# interfacez_vgaaudio_r2_0.net
KiCad netlist of a schematic drawn in EAGLE
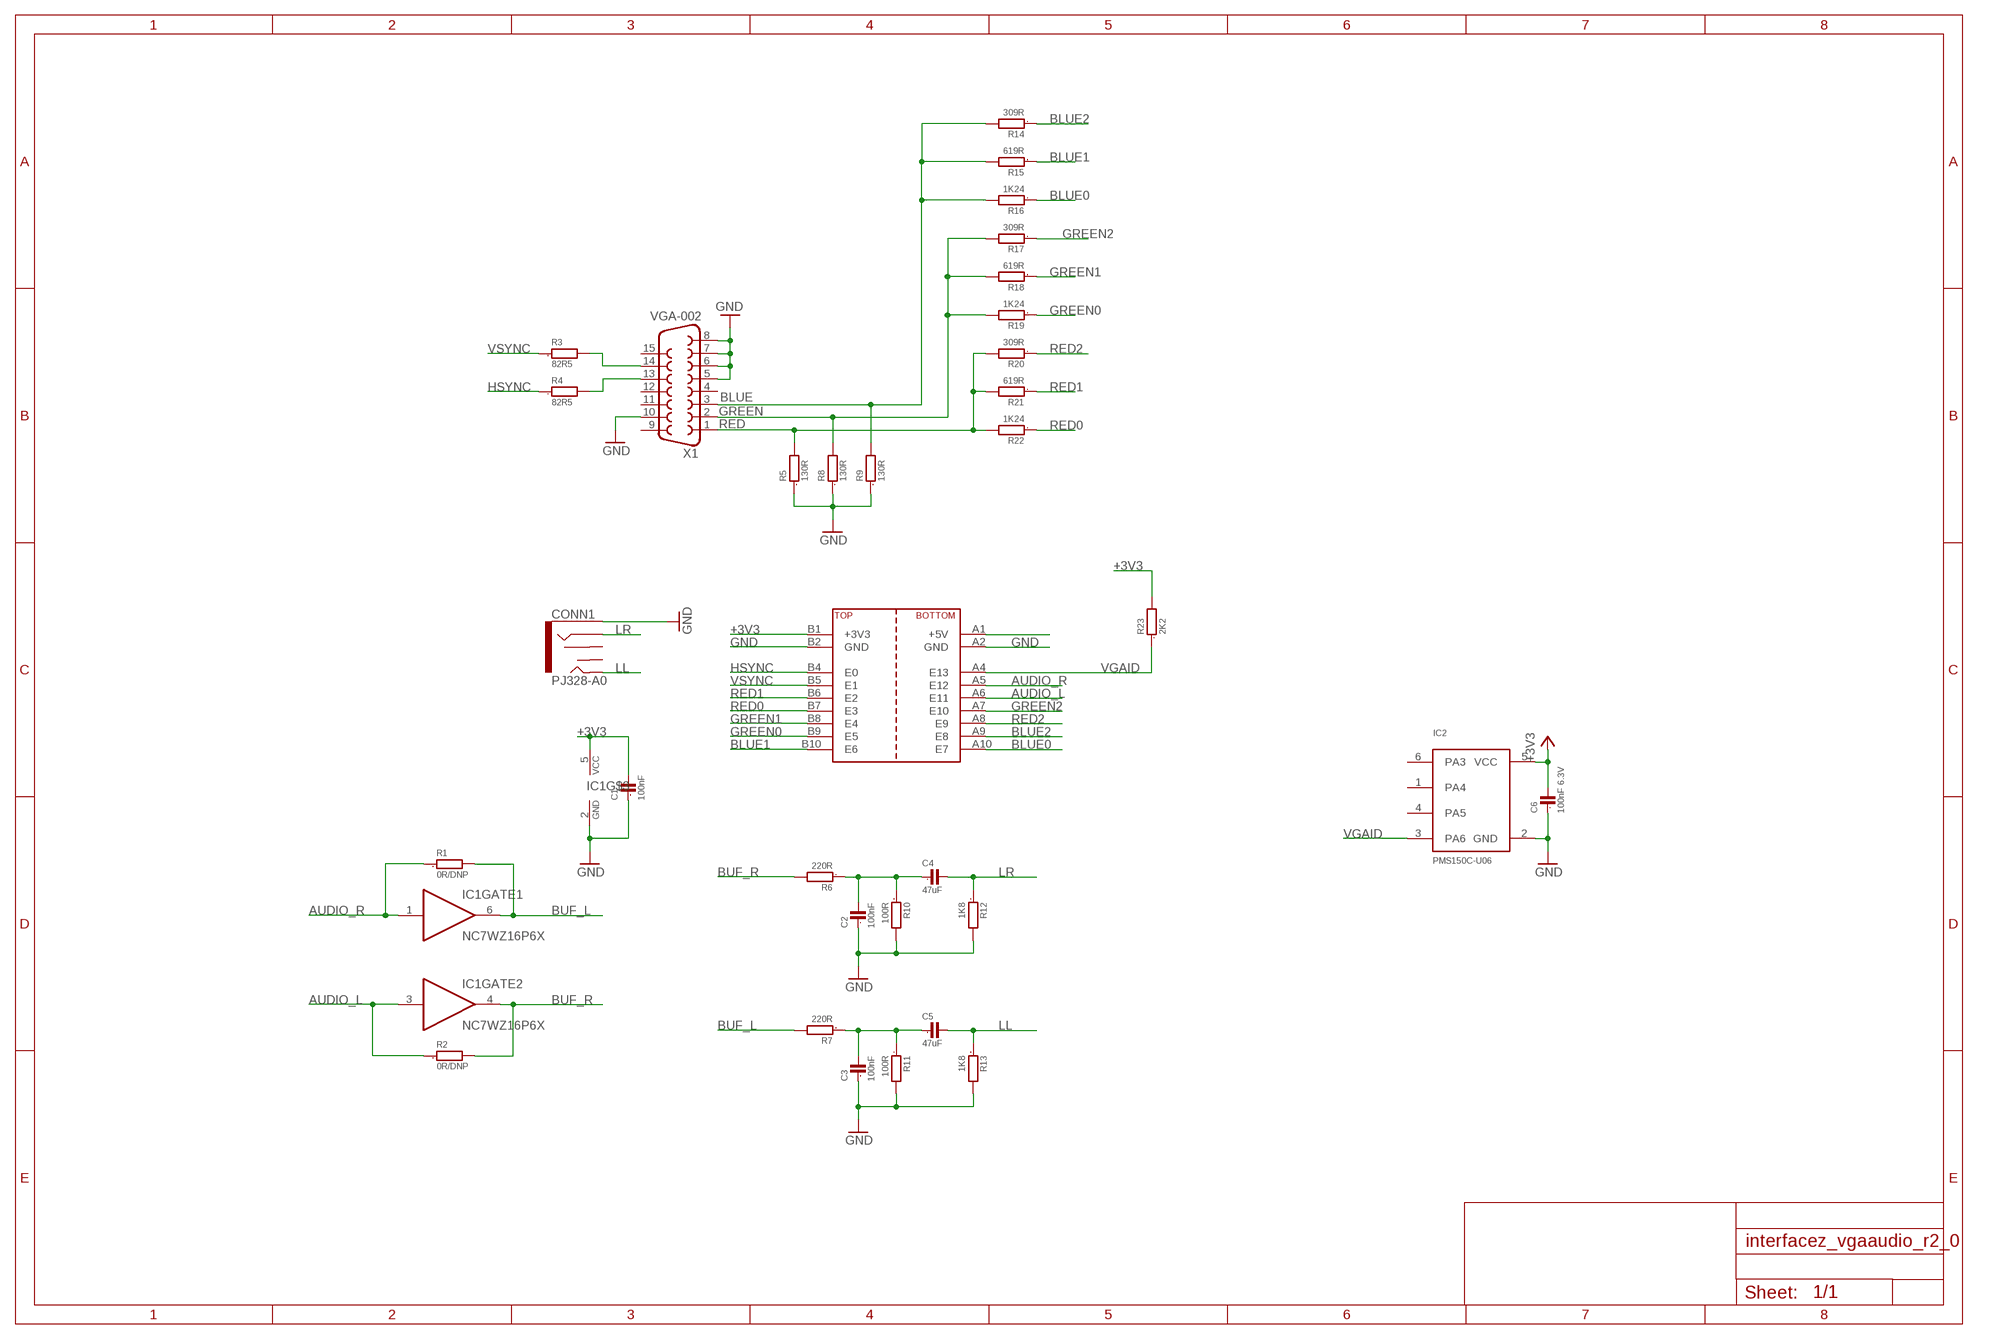
[diagram p0: schematic, sheet 1]

(export (version "E")
  (design (tool "Eeschema 10.0.6"))
  (components
    (comp (ref "C1")
      (value "100nF")
      (footprint "eagle-import:0603")
      (libsource (lib "eagle-import") (part "C0603"))
    )
    (comp (ref "C2")
      (value "100nF")
      (footprint "eagle-import:0603")
      (libsource (lib "eagle-import") (part "C0603"))
    )
    (comp (ref "C3")
      (value "100nF")
      (footprint "eagle-import:0603")
      (libsource (lib "eagle-import") (part "C0603"))
    )
    (comp (ref "C4")
      (value "47uF")
      (footprint "eagle-import:1206")
      (libsource (lib "eagle-import") (part "C1206"))
    )
    (comp (ref "C5")
      (value "47uF")
      (footprint "eagle-import:1206")
      (libsource (lib "eagle-import") (part "C1206"))
    )
    (comp (ref "C6")
      (value "100nF 6.3V")
      (footprint "eagle-import:0603")
      (libsource (lib "eagle-import") (part "C0603"))
    )
    (comp (ref "CONN1")
      (value "PJ328-A0")
      (footprint "eagle-import:PJ328A0")
      (libsource (lib "eagle-import") (part "PJ328-A0"))
    )
    (comp (ref "IC1")
      (value "NC7WZ16P6X")
      (footprint "eagle-import:SC70-6")
      (libsource (lib "eagle-import") (part "NC7WZ07P6X"))
    )
    (comp (ref "IC2")
      (value "PMS150C-U06")
      (footprint "eagle-import:SOT23-6")
      (libsource (lib "eagle-import") (part "PMS150C-U06"))
    )
    (comp (ref "R1")
      (value "0R/DNP")
      (footprint "eagle-import:0603")
      (libsource (lib "eagle-import") (part "R0603"))
    )
    (comp (ref "R2")
      (value "0R/DNP")
      (footprint "eagle-import:0603")
      (libsource (lib "eagle-import") (part "R0603"))
    )
    (comp (ref "R3")
      (value "82R5")
      (footprint "eagle-import:0603")
      (libsource (lib "eagle-import") (part "R0603"))
    )
    (comp (ref "R4")
      (value "82R5")
      (footprint "eagle-import:0603")
      (libsource (lib "eagle-import") (part "R0603"))
    )
    (comp (ref "R5")
      (value "130R")
      (footprint "eagle-import:0603")
      (libsource (lib "eagle-import") (part "R0603"))
    )
    (comp (ref "R6")
      (value "220R")
      (footprint "eagle-import:0603")
      (libsource (lib "eagle-import") (part "R0603"))
    )
    (comp (ref "R7")
      (value "220R")
      (footprint "eagle-import:0603")
      (libsource (lib "eagle-import") (part "R0603"))
    )
    (comp (ref "R8")
      (value "130R")
      (footprint "eagle-import:0603")
      (libsource (lib "eagle-import") (part "R0603"))
    )
    (comp (ref "R9")
      (value "130R")
      (footprint "eagle-import:0603")
      (libsource (lib "eagle-import") (part "R0603"))
    )
    (comp (ref "R10")
      (value "100R")
      (footprint "eagle-import:0603")
      (libsource (lib "eagle-import") (part "R0603"))
    )
    (comp (ref "R11")
      (value "100R")
      (footprint "eagle-import:0603")
      (libsource (lib "eagle-import") (part "R0603"))
    )
    (comp (ref "R12")
      (value "1K8")
      (footprint "eagle-import:0603")
      (libsource (lib "eagle-import") (part "R0603"))
    )
    (comp (ref "R13")
      (value "1K8")
      (footprint "eagle-import:0603")
      (libsource (lib "eagle-import") (part "R0603"))
    )
    (comp (ref "R14")
      (value "309R")
      (footprint "eagle-import:0603")
      (libsource (lib "eagle-import") (part "R0603"))
    )
    (comp (ref "R15")
      (value "619R")
      (footprint "eagle-import:0603")
      (libsource (lib "eagle-import") (part "R0603"))
    )
    (comp (ref "R16")
      (value "1K24")
      (footprint "eagle-import:0603")
      (libsource (lib "eagle-import") (part "R0603"))
    )
    (comp (ref "R17")
      (value "309R")
      (footprint "eagle-import:0603")
      (libsource (lib "eagle-import") (part "R0603"))
    )
    (comp (ref "R18")
      (value "619R")
      (footprint "eagle-import:0603")
      (libsource (lib "eagle-import") (part "R0603"))
    )
    (comp (ref "R19")
      (value "1K24")
      (footprint "eagle-import:0603")
      (libsource (lib "eagle-import") (part "R0603"))
    )
    (comp (ref "R20")
      (value "309R")
      (footprint "eagle-import:0603")
      (libsource (lib "eagle-import") (part "R0603"))
    )
    (comp (ref "R21")
      (value "619R")
      (footprint "eagle-import:0603")
      (libsource (lib "eagle-import") (part "R0603"))
    )
    (comp (ref "R22")
      (value "1K24")
      (footprint "eagle-import:0603")
      (libsource (lib "eagle-import") (part "R0603"))
    )
    (comp (ref "R23")
      (value "2K2")
      (footprint "eagle-import:0603")
      (libsource (lib "eagle-import") (part "R0603"))
    )
    (comp (ref "U$1")
      (value "INTERFACEZ_EDGEDAUGHTER")
      (footprint "eagle-import:INTERFACEZ_EXPANSION_DAUGHTERCARD")
      (libsource (lib "eagle-import") (part "INTERFACEZ_EDGEDAUGHTER"))
    )
    (comp (ref "X1")
      (value "VGA-002")
      (footprint "eagle-import:HDF15H")
      (libsource (lib "eagle-import") (part "F15HDH"))
    )
  )
  (nets
    (net (code "1") (name "+3V3") (class "Default")
      (node (ref "C1") (pin "2") (pinfunction "2_2") (pintype "passive"))
      (node (ref "C6") (pin "2") (pinfunction "2_2") (pintype "passive"))
      (node (ref "IC1") (pin "5") (pinfunction "VCC_5") (pintype "power_in"))
      (node (ref "IC2") (pin "5") (pinfunction "VCC_5") (pintype "power_in"))
      (node (ref "R23") (pin "2") (pinfunction "2_2") (pintype "passive"))
      (node (ref "U$1") (pin "B1") (pinfunction "+3V3_B1") (pintype "power_in"))
    )
    (net (code "2") (name "/AUDIO_L") (class "Default")
      (node (ref "IC1") (pin "3") (pinfunction "I_3") (pintype "input"))
      (node (ref "R2") (pin "1") (pinfunction "1_1") (pintype "passive"))
      (node (ref "U$1") (pin "A6") (pinfunction "E11_A6") (pintype "bidirectional"))
    )
    (net (code "3") (name "/AUDIO_R") (class "Default")
      (node (ref "IC1") (pin "1") (pinfunction "I_1") (pintype "input"))
      (node (ref "R1") (pin "1") (pinfunction "1_1") (pintype "passive"))
      (node (ref "U$1") (pin "A5") (pinfunction "E12_A5") (pintype "bidirectional"))
    )
    (net (code "4") (name "/BLUE") (class "Default")
      (node (ref "R14") (pin "2") (pinfunction "2_2") (pintype "passive"))
      (node (ref "R15") (pin "2") (pinfunction "2_2") (pintype "passive"))
      (node (ref "R16") (pin "2") (pinfunction "2_2") (pintype "passive"))
      (node (ref "R9") (pin "2") (pinfunction "2_2") (pintype "passive"))
      (node (ref "X1") (pin "3") (pinfunction "3_3") (pintype "passive"))
    )
    (net (code "5") (name "/BLUE0") (class "Default")
      (node (ref "R16") (pin "1") (pinfunction "1_1") (pintype "passive"))
      (node (ref "U$1") (pin "A10") (pinfunction "E7_A10") (pintype "bidirectional"))
    )
    (net (code "6") (name "/BLUE1") (class "Default")
      (node (ref "R15") (pin "1") (pinfunction "1_1") (pintype "passive"))
      (node (ref "U$1") (pin "B10") (pinfunction "E6_B10") (pintype "bidirectional"))
    )
    (net (code "7") (name "/BLUE2") (class "Default")
      (node (ref "R14") (pin "1") (pinfunction "1_1") (pintype "passive"))
      (node (ref "U$1") (pin "A9") (pinfunction "E8_A9") (pintype "bidirectional"))
    )
    (net (code "8") (name "/BUF_L") (class "Default")
      (node (ref "IC1") (pin "6") (pinfunction "O_6") (pintype "tri_state"))
      (node (ref "R1") (pin "2") (pinfunction "2_2") (pintype "passive"))
      (node (ref "R7") (pin "2") (pinfunction "2_2") (pintype "passive"))
    )
    (net (code "9") (name "/BUF_R") (class "Default")
      (node (ref "IC1") (pin "4") (pinfunction "O_4") (pintype "tri_state"))
      (node (ref "R2") (pin "2") (pinfunction "2_2") (pintype "passive"))
      (node (ref "R6") (pin "2") (pinfunction "2_2") (pintype "passive"))
    )
    (net (code "10") (name "/GREEN") (class "Default")
      (node (ref "R17") (pin "2") (pinfunction "2_2") (pintype "passive"))
      (node (ref "R18") (pin "2") (pinfunction "2_2") (pintype "passive"))
      (node (ref "R19") (pin "2") (pinfunction "2_2") (pintype "passive"))
      (node (ref "R8") (pin "2") (pinfunction "2_2") (pintype "passive"))
      (node (ref "X1") (pin "2") (pinfunction "2_2") (pintype "passive"))
    )
    (net (code "11") (name "/GREEN0") (class "Default")
      (node (ref "R19") (pin "1") (pinfunction "1_1") (pintype "passive"))
      (node (ref "U$1") (pin "B9") (pinfunction "E5_B9") (pintype "bidirectional"))
    )
    (net (code "12") (name "/GREEN1") (class "Default")
      (node (ref "R18") (pin "1") (pinfunction "1_1") (pintype "passive"))
      (node (ref "U$1") (pin "B8") (pinfunction "E4_B8") (pintype "bidirectional"))
    )
    (net (code "13") (name "/GREEN2") (class "Default")
      (node (ref "R17") (pin "1") (pinfunction "1_1") (pintype "passive"))
      (node (ref "U$1") (pin "A7") (pinfunction "E10_A7") (pintype "bidirectional"))
    )
    (net (code "14") (name "/HSYNC") (class "Default")
      (node (ref "R4") (pin "1") (pinfunction "1_1") (pintype "passive"))
      (node (ref "U$1") (pin "B4") (pinfunction "E0_B4") (pintype "bidirectional"))
    )
    (net (code "15") (name "/LL") (class "Default")
      (node (ref "C5") (pin "2") (pinfunction "2_2") (pintype "passive"))
      (node (ref "CONN1") (pin "2") (pinfunction "TIP_2") (pintype "bidirectional"))
      (node (ref "R13") (pin "1") (pinfunction "1_1") (pintype "passive"))
    )
    (net (code "16") (name "/LR") (class "Default")
      (node (ref "C4") (pin "2") (pinfunction "2_2") (pintype "passive"))
      (node (ref "CONN1") (pin "3") (pinfunction "RING_3") (pintype "bidirectional"))
      (node (ref "R12") (pin "1") (pinfunction "1_1") (pintype "passive"))
    )
    (net (code "17") (name "/RED") (class "Default")
      (node (ref "R20") (pin "2") (pinfunction "2_2") (pintype "passive"))
      (node (ref "R21") (pin "2") (pinfunction "2_2") (pintype "passive"))
      (node (ref "R22") (pin "2") (pinfunction "2_2") (pintype "passive"))
      (node (ref "R5") (pin "2") (pinfunction "2_2") (pintype "passive"))
      (node (ref "X1") (pin "1") (pinfunction "1_1") (pintype "passive"))
    )
    (net (code "18") (name "/RED0") (class "Default")
      (node (ref "R22") (pin "1") (pinfunction "1_1") (pintype "passive"))
      (node (ref "U$1") (pin "B7") (pinfunction "E3_B7") (pintype "bidirectional"))
    )
    (net (code "19") (name "/RED1") (class "Default")
      (node (ref "R21") (pin "1") (pinfunction "1_1") (pintype "passive"))
      (node (ref "U$1") (pin "B6") (pinfunction "E2_B6") (pintype "bidirectional"))
    )
    (net (code "20") (name "/RED2") (class "Default")
      (node (ref "R20") (pin "1") (pinfunction "1_1") (pintype "passive"))
      (node (ref "U$1") (pin "A8") (pinfunction "E9_A8") (pintype "bidirectional"))
    )
    (net (code "21") (name "/VGAID") (class "Default")
      (node (ref "IC2") (pin "3") (pinfunction "PA6_3") (pintype "passive"))
      (node (ref "R23") (pin "1") (pinfunction "1_1") (pintype "passive"))
      (node (ref "U$1") (pin "A4") (pinfunction "E13_A4") (pintype "bidirectional"))
    )
    (net (code "22") (name "/VSYNC") (class "Default")
      (node (ref "R3") (pin "1") (pinfunction "1_1") (pintype "passive"))
      (node (ref "U$1") (pin "B5") (pinfunction "E1_B5") (pintype "bidirectional"))
    )
    (net (code "23") (name "GND") (class "Default")
      (node (ref "C1") (pin "1") (pinfunction "1_1") (pintype "passive"))
      (node (ref "C2") (pin "1") (pinfunction "1_1") (pintype "passive"))
      (node (ref "C3") (pin "1") (pinfunction "1_1") (pintype "passive"))
      (node (ref "C6") (pin "1") (pinfunction "1_1") (pintype "passive"))
      (node (ref "CONN1") (pin "1") (pinfunction "SLEEVE_1") (pintype "bidirectional"))
      (node (ref "IC1") (pin "2") (pinfunction "GND_2") (pintype "power_in"))
      (node (ref "IC2") (pin "2") (pinfunction "GND_2") (pintype "power_in"))
      (node (ref "R10") (pin "2") (pinfunction "2_2") (pintype "passive"))
      (node (ref "R11") (pin "2") (pinfunction "2_2") (pintype "passive"))
      (node (ref "R12") (pin "2") (pinfunction "2_2") (pintype "passive"))
      (node (ref "R13") (pin "2") (pinfunction "2_2") (pintype "passive"))
      (node (ref "R5") (pin "1") (pinfunction "1_1") (pintype "passive"))
      (node (ref "R8") (pin "1") (pinfunction "1_1") (pintype "passive"))
      (node (ref "R9") (pin "1") (pinfunction "1_1") (pintype "passive"))
      (node (ref "U$1") (pin "A2") (pinfunction "GND_A2") (pintype "power_in"))
      (node (ref "U$1") (pin "B2") (pinfunction "GND_B2") (pintype "power_in"))
      (node (ref "X1") (pin "10") (pinfunction "10_10") (pintype "passive"))
      (node (ref "X1") (pin "5") (pinfunction "5_5") (pintype "passive"))
      (node (ref "X1") (pin "6") (pinfunction "6_6") (pintype "passive"))
      (node (ref "X1") (pin "7") (pinfunction "7_7") (pintype "passive"))
      (node (ref "X1") (pin "8") (pinfunction "8_8") (pintype "passive"))
    )
    (net (code "24") (name "Net-(C2-Pad2)") (class "Default")
      (node (ref "C2") (pin "2") (pinfunction "2_2") (pintype "passive"))
      (node (ref "C4") (pin "1") (pinfunction "1_1") (pintype "passive"))
      (node (ref "R10") (pin "1") (pinfunction "1_1") (pintype "passive"))
      (node (ref "R6") (pin "1") (pinfunction "1_1") (pintype "passive"))
    )
    (net (code "25") (name "Net-(C3-Pad2)") (class "Default")
      (node (ref "C3") (pin "2") (pinfunction "2_2") (pintype "passive"))
      (node (ref "C5") (pin "1") (pinfunction "1_1") (pintype "passive"))
      (node (ref "R11") (pin "1") (pinfunction "1_1") (pintype "passive"))
      (node (ref "R7") (pin "1") (pinfunction "1_1") (pintype "passive"))
    )
    (net (code "26") (name "Net-(R3-Pad2)") (class "Default")
      (node (ref "R3") (pin "2") (pinfunction "2_2") (pintype "passive"))
      (node (ref "X1") (pin "14") (pinfunction "14_14") (pintype "passive"))
    )
    (net (code "27") (name "Net-(R4-Pad2)") (class "Default")
      (node (ref "R4") (pin "2") (pinfunction "2_2") (pintype "passive"))
      (node (ref "X1") (pin "13") (pinfunction "13_13") (pintype "passive"))
    )
    (net (code "28") (name "unconnected-(CONN1-RSH-Pad11)") (class "Default")
      (node (ref "CONN1") (pin "11") (pinfunction "RSH_11") (pintype "bidirectional"))
    )
    (net (code "29") (name "unconnected-(CONN1-TSH-Pad10)") (class "Default")
      (node (ref "CONN1") (pin "10") (pinfunction "TSH_10") (pintype "bidirectional"))
    )
    (net (code "30") (name "unconnected-(IC2-PA3-Pad6)") (class "Default")
      (node (ref "IC2") (pin "6") (pinfunction "PA3_6") (pintype "passive"))
    )
    (net (code "31") (name "unconnected-(IC2-PA4-Pad1)") (class "Default")
      (node (ref "IC2") (pin "1") (pinfunction "PA4_1") (pintype "passive"))
    )
    (net (code "32") (name "unconnected-(IC2-PA5-Pad4)") (class "Default")
      (node (ref "IC2") (pin "4") (pinfunction "PA5_4") (pintype "passive"))
    )
    (net (code "33") (name "unconnected-(U$1-+5V-PadA1)") (class "Default")
      (node (ref "U$1") (pin "A1") (pinfunction "+5V_A1") (pintype "power_in"))
    )
    (net (code "34") (name "unconnected-(X1-Pad4)") (class "Default")
      (node (ref "X1") (pin "4") (pinfunction "4_4") (pintype "passive"))
    )
    (net (code "35") (name "unconnected-(X1-Pad9)") (class "Default")
      (node (ref "X1") (pin "9") (pinfunction "9_9") (pintype "passive"))
    )
    (net (code "36") (name "unconnected-(X1-Pad11)") (class "Default")
      (node (ref "X1") (pin "11") (pinfunction "11_11") (pintype "passive"))
    )
    (net (code "37") (name "unconnected-(X1-Pad12)") (class "Default")
      (node (ref "X1") (pin "12") (pinfunction "12_12") (pintype "passive"))
    )
    (net (code "38") (name "unconnected-(X1-Pad15)") (class "Default")
      (node (ref "X1") (pin "15") (pinfunction "15_15") (pintype "passive"))
    )
  )
)
